# teensyShield1_4.net
KiCad netlist of a schematic drawn in EAGLE
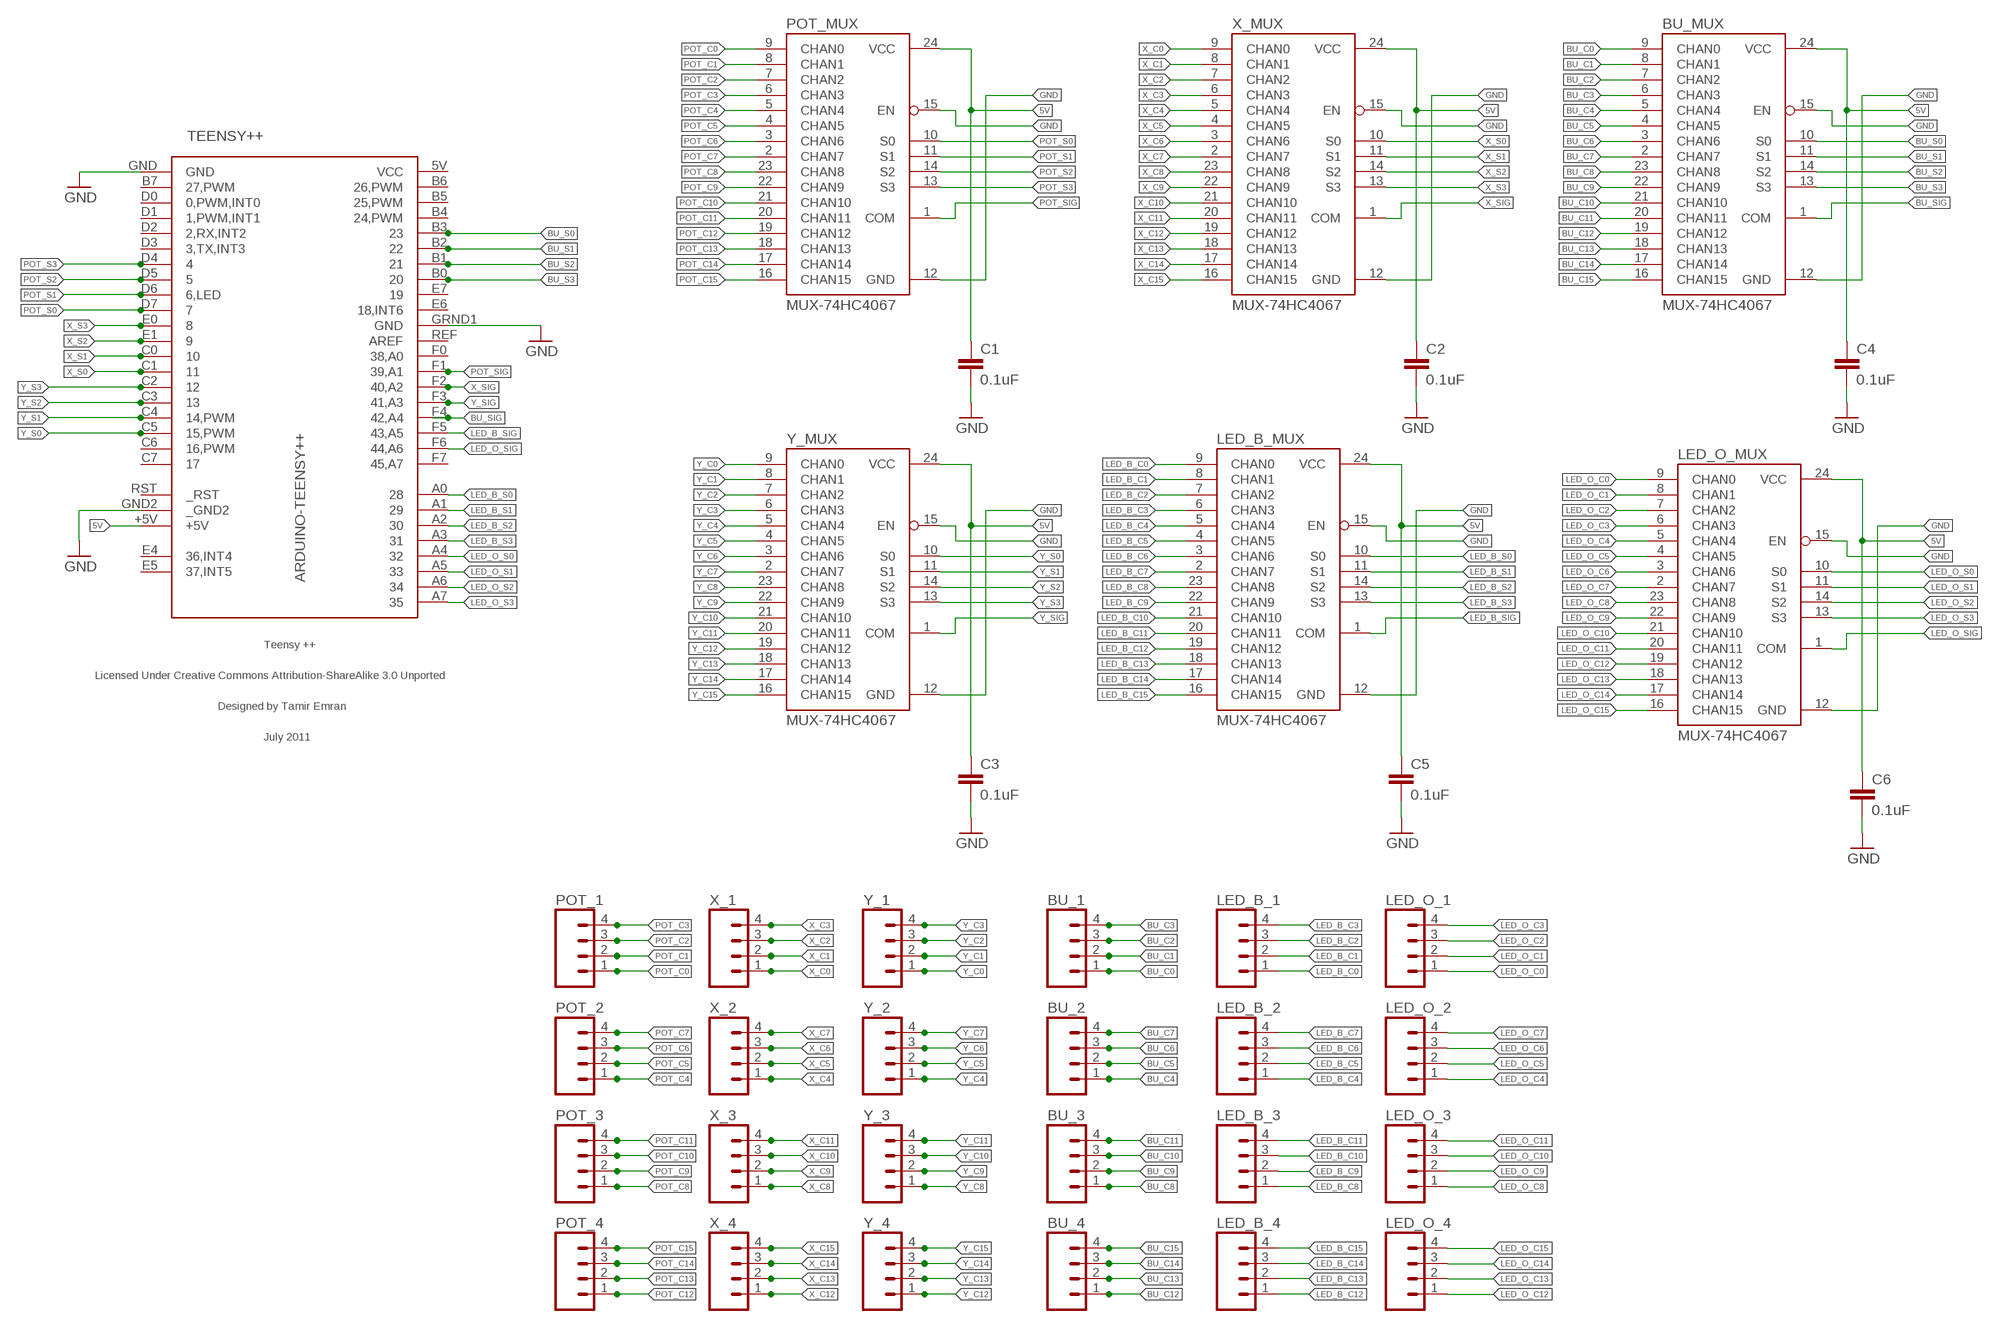
[diagram p0: schematic, sheet 1]

(export (version "E")
  (design (tool "Eeschema 10.0.6"))
  (components
    (comp (ref "BU_1")
      (value "M04NO_SILK_ALL_ROUND")
      (footprint "eagle-import:1X04_NO_SILK_ALL_ROUND")
      (libsource (lib "eagle-import") (part "M04NO_SILK_ALL_ROUND"))
    )
    (comp (ref "BU_2")
      (value "M04NO_SILK_ALL_ROUND")
      (footprint "eagle-import:1X04_NO_SILK_ALL_ROUND")
      (libsource (lib "eagle-import") (part "M04NO_SILK_ALL_ROUND"))
    )
    (comp (ref "BU_3")
      (value "M04NO_SILK_ALL_ROUND")
      (footprint "eagle-import:1X04_NO_SILK_ALL_ROUND")
      (libsource (lib "eagle-import") (part "M04NO_SILK_ALL_ROUND"))
    )
    (comp (ref "BU_4")
      (value "M04NO_SILK_ALL_ROUND")
      (footprint "eagle-import:1X04_NO_SILK_ALL_ROUND")
      (libsource (lib "eagle-import") (part "M04NO_SILK_ALL_ROUND"))
    )
    (comp (ref "BU_MUX")
      (value "MUX-74HC4067")
      (footprint "eagle-import:SSOP24")
      (libsource (lib "eagle-import") (part "MUX-74HC4067SMD"))
    )
    (comp (ref "C1")
      (value "0.1uF")
      (footprint "eagle-import:0603")
      (libsource (lib "eagle-import") (part "CAP0603"))
    )
    (comp (ref "C2")
      (value "0.1uF")
      (footprint "eagle-import:0603")
      (libsource (lib "eagle-import") (part "CAP0603"))
    )
    (comp (ref "C3")
      (value "0.1uF")
      (footprint "eagle-import:0603")
      (libsource (lib "eagle-import") (part "CAP0603"))
    )
    (comp (ref "C4")
      (value "0.1uF")
      (footprint "eagle-import:0603")
      (libsource (lib "eagle-import") (part "CAP0603"))
    )
    (comp (ref "C5")
      (value "0.1uF")
      (footprint "eagle-import:0603")
      (libsource (lib "eagle-import") (part "CAP0603"))
    )
    (comp (ref "C6")
      (value "0.1uF")
      (footprint "eagle-import:0603")
      (libsource (lib "eagle-import") (part "CAP0603"))
    )
    (comp (ref "LED_B_1")
      (value "M04NO_SILK_ALL_ROUND")
      (footprint "eagle-import:1X04_NO_SILK_ALL_ROUND")
      (libsource (lib "eagle-import") (part "M04NO_SILK_ALL_ROUND"))
    )
    (comp (ref "LED_B_2")
      (value "M04NO_SILK_ALL_ROUND")
      (footprint "eagle-import:1X04_NO_SILK_ALL_ROUND")
      (libsource (lib "eagle-import") (part "M04NO_SILK_ALL_ROUND"))
    )
    (comp (ref "LED_B_3")
      (value "M04NO_SILK_ALL_ROUND")
      (footprint "eagle-import:1X04_NO_SILK_ALL_ROUND")
      (libsource (lib "eagle-import") (part "M04NO_SILK_ALL_ROUND"))
    )
    (comp (ref "LED_B_4")
      (value "M04NO_SILK_ALL_ROUND")
      (footprint "eagle-import:1X04_NO_SILK_ALL_ROUND")
      (libsource (lib "eagle-import") (part "M04NO_SILK_ALL_ROUND"))
    )
    (comp (ref "LED_B_MUX")
      (value "MUX-74HC4067")
      (footprint "eagle-import:SSOP24")
      (libsource (lib "eagle-import") (part "MUX-74HC4067SMD"))
    )
    (comp (ref "LED_O_1")
      (value "M04NO_SILK_ALL_ROUND")
      (footprint "eagle-import:1X04_NO_SILK_ALL_ROUND")
      (libsource (lib "eagle-import") (part "M04NO_SILK_ALL_ROUND"))
    )
    (comp (ref "LED_O_2")
      (value "M04NO_SILK_ALL_ROUND")
      (footprint "eagle-import:1X04_NO_SILK_ALL_ROUND")
      (libsource (lib "eagle-import") (part "M04NO_SILK_ALL_ROUND"))
    )
    (comp (ref "LED_O_3")
      (value "M04NO_SILK_ALL_ROUND")
      (footprint "eagle-import:1X04_NO_SILK_ALL_ROUND")
      (libsource (lib "eagle-import") (part "M04NO_SILK_ALL_ROUND"))
    )
    (comp (ref "LED_O_4")
      (value "M04NO_SILK_ALL_ROUND")
      (footprint "eagle-import:1X04_NO_SILK_ALL_ROUND")
      (libsource (lib "eagle-import") (part "M04NO_SILK_ALL_ROUND"))
    )
    (comp (ref "LED_O_MUX")
      (value "MUX-74HC4067")
      (footprint "eagle-import:SSOP24")
      (libsource (lib "eagle-import") (part "MUX-74HC4067SMD"))
    )
    (comp (ref "POT_1")
      (value "M04NO_SILK_ALL_ROUND")
      (footprint "eagle-import:1X04_NO_SILK_ALL_ROUND")
      (libsource (lib "eagle-import") (part "M04NO_SILK_ALL_ROUND"))
    )
    (comp (ref "POT_2")
      (value "M04NO_SILK_ALL_ROUND")
      (footprint "eagle-import:1X04_NO_SILK_ALL_ROUND")
      (libsource (lib "eagle-import") (part "M04NO_SILK_ALL_ROUND"))
    )
    (comp (ref "POT_3")
      (value "M04NO_SILK_ALL_ROUND")
      (footprint "eagle-import:1X04_NO_SILK_ALL_ROUND")
      (libsource (lib "eagle-import") (part "M04NO_SILK_ALL_ROUND"))
    )
    (comp (ref "POT_4")
      (value "M04NO_SILK_ALL_ROUND")
      (footprint "eagle-import:1X04_NO_SILK_ALL_ROUND")
      (libsource (lib "eagle-import") (part "M04NO_SILK_ALL_ROUND"))
    )
    (comp (ref "POT_MUX")
      (value "MUX-74HC4067")
      (footprint "eagle-import:SSOP24")
      (libsource (lib "eagle-import") (part "MUX-74HC4067SMD"))
    )
    (comp (ref "TEENSY++")
      (value "ARDUINO-TEENSY++")
      (footprint "eagle-import:TEENSY++")
      (libsource (lib "eagle-import") (part "ARDUINO-TEENSY++"))
    )
    (comp (ref "X_1")
      (value "M04NO_SILK_ALL_ROUND")
      (footprint "eagle-import:1X04_NO_SILK_ALL_ROUND")
      (libsource (lib "eagle-import") (part "M04NO_SILK_ALL_ROUND"))
    )
    (comp (ref "X_2")
      (value "M04NO_SILK_ALL_ROUND")
      (footprint "eagle-import:1X04_NO_SILK_ALL_ROUND")
      (libsource (lib "eagle-import") (part "M04NO_SILK_ALL_ROUND"))
    )
    (comp (ref "X_3")
      (value "M04NO_SILK_ALL_ROUND")
      (footprint "eagle-import:1X04_NO_SILK_ALL_ROUND")
      (libsource (lib "eagle-import") (part "M04NO_SILK_ALL_ROUND"))
    )
    (comp (ref "X_4")
      (value "M04NO_SILK_ALL_ROUND")
      (footprint "eagle-import:1X04_NO_SILK_ALL_ROUND")
      (libsource (lib "eagle-import") (part "M04NO_SILK_ALL_ROUND"))
    )
    (comp (ref "X_MUX")
      (value "MUX-74HC4067")
      (footprint "eagle-import:SSOP24")
      (libsource (lib "eagle-import") (part "MUX-74HC4067SMD"))
    )
    (comp (ref "Y_1")
      (value "M04NO_SILK_ALL_ROUND")
      (footprint "eagle-import:1X04_NO_SILK_ALL_ROUND")
      (libsource (lib "eagle-import") (part "M04NO_SILK_ALL_ROUND"))
    )
    (comp (ref "Y_2")
      (value "M04NO_SILK_ALL_ROUND")
      (footprint "eagle-import:1X04_NO_SILK_ALL_ROUND")
      (libsource (lib "eagle-import") (part "M04NO_SILK_ALL_ROUND"))
    )
    (comp (ref "Y_3")
      (value "M04NO_SILK_ALL_ROUND")
      (footprint "eagle-import:1X04_NO_SILK_ALL_ROUND")
      (libsource (lib "eagle-import") (part "M04NO_SILK_ALL_ROUND"))
    )
    (comp (ref "Y_4")
      (value "M04NO_SILK_ALL_ROUND")
      (footprint "eagle-import:1X04_NO_SILK_ALL_ROUND")
      (libsource (lib "eagle-import") (part "M04NO_SILK_ALL_ROUND"))
    )
    (comp (ref "Y_MUX")
      (value "MUX-74HC4067")
      (footprint "eagle-import:SSOP24")
      (libsource (lib "eagle-import") (part "MUX-74HC4067SMD"))
    )
  )
  (nets
    (net (code "1") (name "/VCC") (class "Default")
      (node (ref "TEENSY++") (pin "5V") (pinfunction "VCC_5V") (pintype "power_in"))
    )
    (net (code "2") (name "5V") (class "Default")
      (node (ref "BU_MUX") (pin "24") (pinfunction "VCC_24") (pintype "bidirectional"))
      (node (ref "C1") (pin "1") (pinfunction "1_1") (pintype "passive"))
      (node (ref "C2") (pin "1") (pinfunction "1_1") (pintype "passive"))
      (node (ref "C3") (pin "1") (pinfunction "1_1") (pintype "passive"))
      (node (ref "C4") (pin "1") (pinfunction "1_1") (pintype "passive"))
      (node (ref "C5") (pin "1") (pinfunction "1_1") (pintype "passive"))
      (node (ref "C6") (pin "1") (pinfunction "1_1") (pintype "passive"))
      (node (ref "LED_B_MUX") (pin "24") (pinfunction "VCC_24") (pintype "bidirectional"))
      (node (ref "LED_O_MUX") (pin "24") (pinfunction "VCC_24") (pintype "bidirectional"))
      (node (ref "POT_MUX") (pin "24") (pinfunction "VCC_24") (pintype "bidirectional"))
      (node (ref "X_MUX") (pin "24") (pinfunction "VCC_24") (pintype "bidirectional"))
      (node (ref "Y_MUX") (pin "24") (pinfunction "VCC_24") (pintype "bidirectional"))
    )
    (net (code "3") (name "BU_C0") (class "Default")
      (node (ref "BU_1") (pin "1") (pinfunction "1_1") (pintype "passive"))
      (node (ref "BU_MUX") (pin "9") (pinfunction "CHAN0_9") (pintype "bidirectional"))
    )
    (net (code "4") (name "BU_C1") (class "Default")
      (node (ref "BU_1") (pin "2") (pinfunction "2_2") (pintype "passive"))
      (node (ref "BU_MUX") (pin "8") (pinfunction "CHAN1_8") (pintype "bidirectional"))
    )
    (net (code "5") (name "BU_C2") (class "Default")
      (node (ref "BU_1") (pin "3") (pinfunction "3_3") (pintype "passive"))
      (node (ref "BU_MUX") (pin "7") (pinfunction "CHAN2_7") (pintype "bidirectional"))
    )
    (net (code "6") (name "BU_C3") (class "Default")
      (node (ref "BU_1") (pin "4") (pinfunction "4_4") (pintype "passive"))
      (node (ref "BU_MUX") (pin "6") (pinfunction "CHAN3_6") (pintype "bidirectional"))
    )
    (net (code "7") (name "BU_C4") (class "Default")
      (node (ref "BU_2") (pin "1") (pinfunction "1_1") (pintype "passive"))
      (node (ref "BU_MUX") (pin "5") (pinfunction "CHAN4_5") (pintype "bidirectional"))
    )
    (net (code "8") (name "BU_C5") (class "Default")
      (node (ref "BU_2") (pin "2") (pinfunction "2_2") (pintype "passive"))
      (node (ref "BU_MUX") (pin "4") (pinfunction "CHAN5_4") (pintype "bidirectional"))
    )
    (net (code "9") (name "BU_C6") (class "Default")
      (node (ref "BU_2") (pin "3") (pinfunction "3_3") (pintype "passive"))
      (node (ref "BU_MUX") (pin "3") (pinfunction "CHAN6_3") (pintype "bidirectional"))
    )
    (net (code "10") (name "BU_C7") (class "Default")
      (node (ref "BU_2") (pin "4") (pinfunction "4_4") (pintype "passive"))
      (node (ref "BU_MUX") (pin "2") (pinfunction "CHAN7_2") (pintype "bidirectional"))
    )
    (net (code "11") (name "BU_C8") (class "Default")
      (node (ref "BU_3") (pin "1") (pinfunction "1_1") (pintype "passive"))
      (node (ref "BU_MUX") (pin "23") (pinfunction "CHAN8_23") (pintype "bidirectional"))
    )
    (net (code "12") (name "BU_C9") (class "Default")
      (node (ref "BU_3") (pin "2") (pinfunction "2_2") (pintype "passive"))
      (node (ref "BU_MUX") (pin "22") (pinfunction "CHAN9_22") (pintype "bidirectional"))
    )
    (net (code "13") (name "BU_C10") (class "Default")
      (node (ref "BU_3") (pin "3") (pinfunction "3_3") (pintype "passive"))
      (node (ref "BU_MUX") (pin "21") (pinfunction "CHAN10_21") (pintype "bidirectional"))
    )
    (net (code "14") (name "BU_C11") (class "Default")
      (node (ref "BU_3") (pin "4") (pinfunction "4_4") (pintype "passive"))
      (node (ref "BU_MUX") (pin "20") (pinfunction "CHAN11_20") (pintype "bidirectional"))
    )
    (net (code "15") (name "BU_C12") (class "Default")
      (node (ref "BU_4") (pin "1") (pinfunction "1_1") (pintype "passive"))
      (node (ref "BU_MUX") (pin "19") (pinfunction "CHAN12_19") (pintype "bidirectional"))
    )
    (net (code "16") (name "BU_C13") (class "Default")
      (node (ref "BU_4") (pin "2") (pinfunction "2_2") (pintype "passive"))
      (node (ref "BU_MUX") (pin "18") (pinfunction "CHAN13_18") (pintype "bidirectional"))
    )
    (net (code "17") (name "BU_C14") (class "Default")
      (node (ref "BU_4") (pin "3") (pinfunction "3_3") (pintype "passive"))
      (node (ref "BU_MUX") (pin "17") (pinfunction "CHAN14_17") (pintype "bidirectional"))
    )
    (net (code "18") (name "BU_C15") (class "Default")
      (node (ref "BU_4") (pin "4") (pinfunction "4_4") (pintype "passive"))
      (node (ref "BU_MUX") (pin "16") (pinfunction "CHAN15_16") (pintype "bidirectional"))
    )
    (net (code "19") (name "BU_S0") (class "Default")
      (node (ref "BU_MUX") (pin "10") (pinfunction "S0_10") (pintype "input"))
      (node (ref "TEENSY++") (pin "B3") (pinfunction "23_B3") (pintype "bidirectional"))
    )
    (net (code "20") (name "BU_S1") (class "Default")
      (node (ref "BU_MUX") (pin "11") (pinfunction "S1_11") (pintype "input"))
      (node (ref "TEENSY++") (pin "B2") (pinfunction "22_B2") (pintype "bidirectional"))
    )
    (net (code "21") (name "BU_S2") (class "Default")
      (node (ref "BU_MUX") (pin "14") (pinfunction "S2_14") (pintype "input"))
      (node (ref "TEENSY++") (pin "B1") (pinfunction "21_B1") (pintype "bidirectional"))
    )
    (net (code "22") (name "BU_S3") (class "Default")
      (node (ref "BU_MUX") (pin "13") (pinfunction "S3_13") (pintype "input"))
      (node (ref "TEENSY++") (pin "B0") (pinfunction "20_B0") (pintype "bidirectional"))
    )
    (net (code "23") (name "BU_SIG") (class "Default")
      (node (ref "BU_MUX") (pin "1") (pinfunction "COM_1") (pintype "bidirectional"))
      (node (ref "TEENSY++") (pin "F4") (pinfunction "42,A4_F4") (pintype "bidirectional"))
    )
    (net (code "24") (name "GND") (class "Default")
      (node (ref "BU_MUX") (pin "12") (pinfunction "GND_12") (pintype "bidirectional"))
      (node (ref "BU_MUX") (pin "15") (pinfunction "EN_15") (pintype "input"))
      (node (ref "C1") (pin "2") (pinfunction "2_2") (pintype "passive"))
      (node (ref "C2") (pin "2") (pinfunction "2_2") (pintype "passive"))
      (node (ref "C3") (pin "2") (pinfunction "2_2") (pintype "passive"))
      (node (ref "C4") (pin "2") (pinfunction "2_2") (pintype "passive"))
      (node (ref "C5") (pin "2") (pinfunction "2_2") (pintype "passive"))
      (node (ref "C6") (pin "2") (pinfunction "2_2") (pintype "passive"))
      (node (ref "LED_B_MUX") (pin "12") (pinfunction "GND_12") (pintype "bidirectional"))
      (node (ref "LED_B_MUX") (pin "15") (pinfunction "EN_15") (pintype "input"))
      (node (ref "LED_O_MUX") (pin "12") (pinfunction "GND_12") (pintype "bidirectional"))
      (node (ref "LED_O_MUX") (pin "15") (pinfunction "EN_15") (pintype "input"))
      (node (ref "POT_MUX") (pin "12") (pinfunction "GND_12") (pintype "bidirectional"))
      (node (ref "POT_MUX") (pin "15") (pinfunction "EN_15") (pintype "input"))
      (node (ref "TEENSY++") (pin "GND") (pinfunction "GND_GND") (pintype "power_in"))
      (node (ref "TEENSY++") (pin "GND2") (pinfunction "_GND2_GND2") (pintype "power_in"))
      (node (ref "TEENSY++") (pin "GRND1") (pinfunction "GND_GRND1") (pintype "power_in"))
      (node (ref "X_MUX") (pin "12") (pinfunction "GND_12") (pintype "bidirectional"))
      (node (ref "X_MUX") (pin "15") (pinfunction "EN_15") (pintype "input"))
      (node (ref "Y_MUX") (pin "12") (pinfunction "GND_12") (pintype "bidirectional"))
      (node (ref "Y_MUX") (pin "15") (pinfunction "EN_15") (pintype "input"))
    )
    (net (code "25") (name "LED_B_C0") (class "Default")
      (node (ref "LED_B_1") (pin "1") (pinfunction "1_1") (pintype "passive"))
      (node (ref "LED_B_MUX") (pin "9") (pinfunction "CHAN0_9") (pintype "bidirectional"))
    )
    (net (code "26") (name "LED_B_C1") (class "Default")
      (node (ref "LED_B_1") (pin "2") (pinfunction "2_2") (pintype "passive"))
      (node (ref "LED_B_MUX") (pin "8") (pinfunction "CHAN1_8") (pintype "bidirectional"))
    )
    (net (code "27") (name "LED_B_C2") (class "Default")
      (node (ref "LED_B_1") (pin "3") (pinfunction "3_3") (pintype "passive"))
      (node (ref "LED_B_MUX") (pin "7") (pinfunction "CHAN2_7") (pintype "bidirectional"))
    )
    (net (code "28") (name "LED_B_C3") (class "Default")
      (node (ref "LED_B_1") (pin "4") (pinfunction "4_4") (pintype "passive"))
      (node (ref "LED_B_MUX") (pin "6") (pinfunction "CHAN3_6") (pintype "bidirectional"))
    )
    (net (code "29") (name "LED_B_C4") (class "Default")
      (node (ref "LED_B_2") (pin "1") (pinfunction "1_1") (pintype "passive"))
      (node (ref "LED_B_MUX") (pin "5") (pinfunction "CHAN4_5") (pintype "bidirectional"))
    )
    (net (code "30") (name "LED_B_C5") (class "Default")
      (node (ref "LED_B_2") (pin "2") (pinfunction "2_2") (pintype "passive"))
      (node (ref "LED_B_MUX") (pin "4") (pinfunction "CHAN5_4") (pintype "bidirectional"))
    )
    (net (code "31") (name "LED_B_C6") (class "Default")
      (node (ref "LED_B_2") (pin "3") (pinfunction "3_3") (pintype "passive"))
      (node (ref "LED_B_MUX") (pin "3") (pinfunction "CHAN6_3") (pintype "bidirectional"))
    )
    (net (code "32") (name "LED_B_C7") (class "Default")
      (node (ref "LED_B_2") (pin "4") (pinfunction "4_4") (pintype "passive"))
      (node (ref "LED_B_MUX") (pin "2") (pinfunction "CHAN7_2") (pintype "bidirectional"))
    )
    (net (code "33") (name "LED_B_C8") (class "Default")
      (node (ref "LED_B_3") (pin "1") (pinfunction "1_1") (pintype "passive"))
      (node (ref "LED_B_MUX") (pin "23") (pinfunction "CHAN8_23") (pintype "bidirectional"))
    )
    (net (code "34") (name "LED_B_C9") (class "Default")
      (node (ref "LED_B_3") (pin "2") (pinfunction "2_2") (pintype "passive"))
      (node (ref "LED_B_MUX") (pin "22") (pinfunction "CHAN9_22") (pintype "bidirectional"))
    )
    (net (code "35") (name "LED_B_C10") (class "Default")
      (node (ref "LED_B_3") (pin "3") (pinfunction "3_3") (pintype "passive"))
      (node (ref "LED_B_MUX") (pin "21") (pinfunction "CHAN10_21") (pintype "bidirectional"))
    )
    (net (code "36") (name "LED_B_C11") (class "Default")
      (node (ref "LED_B_3") (pin "4") (pinfunction "4_4") (pintype "passive"))
      (node (ref "LED_B_MUX") (pin "20") (pinfunction "CHAN11_20") (pintype "bidirectional"))
    )
    (net (code "37") (name "LED_B_C12") (class "Default")
      (node (ref "LED_B_4") (pin "1") (pinfunction "1_1") (pintype "passive"))
      (node (ref "LED_B_MUX") (pin "19") (pinfunction "CHAN12_19") (pintype "bidirectional"))
    )
    (net (code "38") (name "LED_B_C13") (class "Default")
      (node (ref "LED_B_4") (pin "2") (pinfunction "2_2") (pintype "passive"))
      (node (ref "LED_B_MUX") (pin "18") (pinfunction "CHAN13_18") (pintype "bidirectional"))
    )
    (net (code "39") (name "LED_B_C14") (class "Default")
      (node (ref "LED_B_4") (pin "3") (pinfunction "3_3") (pintype "passive"))
      (node (ref "LED_B_MUX") (pin "17") (pinfunction "CHAN14_17") (pintype "bidirectional"))
    )
    (net (code "40") (name "LED_B_C15") (class "Default")
      (node (ref "LED_B_4") (pin "4") (pinfunction "4_4") (pintype "passive"))
      (node (ref "LED_B_MUX") (pin "16") (pinfunction "CHAN15_16") (pintype "bidirectional"))
    )
    (net (code "41") (name "LED_B_S0") (class "Default")
      (node (ref "LED_B_MUX") (pin "10") (pinfunction "S0_10") (pintype "input"))
      (node (ref "TEENSY++") (pin "A0") (pinfunction "28_A0") (pintype "bidirectional"))
    )
    (net (code "42") (name "LED_B_S1") (class "Default")
      (node (ref "LED_B_MUX") (pin "11") (pinfunction "S1_11") (pintype "input"))
      (node (ref "TEENSY++") (pin "A1") (pinfunction "29_A1") (pintype "bidirectional"))
    )
    (net (code "43") (name "LED_B_S2") (class "Default")
      (node (ref "LED_B_MUX") (pin "14") (pinfunction "S2_14") (pintype "input"))
      (node (ref "TEENSY++") (pin "A2") (pinfunction "30_A2") (pintype "bidirectional"))
    )
    (net (code "44") (name "LED_B_S3") (class "Default")
      (node (ref "LED_B_MUX") (pin "13") (pinfunction "S3_13") (pintype "input"))
      (node (ref "TEENSY++") (pin "A3") (pinfunction "31_A3") (pintype "bidirectional"))
    )
    (net (code "45") (name "LED_B_SIG") (class "Default")
      (node (ref "LED_B_MUX") (pin "1") (pinfunction "COM_1") (pintype "bidirectional"))
    )
    (net (code "46") (name "LED_O_C0") (class "Default")
      (node (ref "LED_O_1") (pin "1") (pinfunction "1_1") (pintype "passive"))
      (node (ref "LED_O_MUX") (pin "9") (pinfunction "CHAN0_9") (pintype "bidirectional"))
    )
    (net (code "47") (name "LED_O_C1") (class "Default")
      (node (ref "LED_O_1") (pin "2") (pinfunction "2_2") (pintype "passive"))
      (node (ref "LED_O_MUX") (pin "8") (pinfunction "CHAN1_8") (pintype "bidirectional"))
    )
    (net (code "48") (name "LED_O_C2") (class "Default")
      (node (ref "LED_O_1") (pin "3") (pinfunction "3_3") (pintype "passive"))
      (node (ref "LED_O_MUX") (pin "7") (pinfunction "CHAN2_7") (pintype "bidirectional"))
    )
    (net (code "49") (name "LED_O_C3") (class "Default")
      (node (ref "LED_O_1") (pin "4") (pinfunction "4_4") (pintype "passive"))
      (node (ref "LED_O_MUX") (pin "6") (pinfunction "CHAN3_6") (pintype "bidirectional"))
    )
    (net (code "50") (name "LED_O_C4") (class "Default")
      (node (ref "LED_O_2") (pin "1") (pinfunction "1_1") (pintype "passive"))
      (node (ref "LED_O_MUX") (pin "5") (pinfunction "CHAN4_5") (pintype "bidirectional"))
    )
    (net (code "51") (name "LED_O_C5") (class "Default")
      (node (ref "LED_O_2") (pin "2") (pinfunction "2_2") (pintype "passive"))
      (node (ref "LED_O_MUX") (pin "4") (pinfunction "CHAN5_4") (pintype "bidirectional"))
    )
    (net (code "52") (name "LED_O_C6") (class "Default")
      (node (ref "LED_O_2") (pin "3") (pinfunction "3_3") (pintype "passive"))
      (node (ref "LED_O_MUX") (pin "3") (pinfunction "CHAN6_3") (pintype "bidirectional"))
    )
    (net (code "53") (name "LED_O_C7") (class "Default")
      (node (ref "LED_O_2") (pin "4") (pinfunction "4_4") (pintype "passive"))
      (node (ref "LED_O_MUX") (pin "2") (pinfunction "CHAN7_2") (pintype "bidirectional"))
    )
    (net (code "54") (name "LED_O_C8") (class "Default")
      (node (ref "LED_O_3") (pin "1") (pinfunction "1_1") (pintype "passive"))
      (node (ref "LED_O_MUX") (pin "23") (pinfunction "CHAN8_23") (pintype "bidirectional"))
    )
    (net (code "55") (name "LED_O_C9") (class "Default")
      (node (ref "LED_O_3") (pin "2") (pinfunction "2_2") (pintype "passive"))
      (node (ref "LED_O_MUX") (pin "22") (pinfunction "CHAN9_22") (pintype "bidirectional"))
    )
    (net (code "56") (name "LED_O_C10") (class "Default")
      (node (ref "LED_O_3") (pin "3") (pinfunction "3_3") (pintype "passive"))
      (node (ref "LED_O_MUX") (pin "21") (pinfunction "CHAN10_21") (pintype "bidirectional"))
    )
    (net (code "57") (name "LED_O_C11") (class "Default")
      (node (ref "LED_O_3") (pin "4") (pinfunction "4_4") (pintype "passive"))
      (node (ref "LED_O_MUX") (pin "20") (pinfunction "CHAN11_20") (pintype "bidirectional"))
    )
    (net (code "58") (name "LED_O_C12") (class "Default")
      (node (ref "LED_O_4") (pin "1") (pinfunction "1_1") (pintype "passive"))
      (node (ref "LED_O_MUX") (pin "19") (pinfunction "CHAN12_19") (pintype "bidirectional"))
    )
    (net (code "59") (name "LED_O_C13") (class "Default")
      (node (ref "LED_O_4") (pin "2") (pinfunction "2_2") (pintype "passive"))
      (node (ref "LED_O_MUX") (pin "18") (pinfunction "CHAN13_18") (pintype "bidirectional"))
    )
    (net (code "60") (name "LED_O_C14") (class "Default")
      (node (ref "LED_O_4") (pin "3") (pinfunction "3_3") (pintype "passive"))
      (node (ref "LED_O_MUX") (pin "17") (pinfunction "CHAN14_17") (pintype "bidirectional"))
    )
    (net (code "61") (name "LED_O_C15") (class "Default")
      (node (ref "LED_O_4") (pin "4") (pinfunction "4_4") (pintype "passive"))
      (node (ref "LED_O_MUX") (pin "16") (pinfunction "CHAN15_16") (pintype "bidirectional"))
    )
    (net (code "62") (name "LED_O_S0") (class "Default")
      (node (ref "LED_O_MUX") (pin "10") (pinfunction "S0_10") (pintype "input"))
      (node (ref "TEENSY++") (pin "A4") (pinfunction "32_A4") (pintype "bidirectional"))
    )
    (net (code "63") (name "LED_O_S1") (class "Default")
      (node (ref "LED_O_MUX") (pin "11") (pinfunction "S1_11") (pintype "input"))
      (node (ref "TEENSY++") (pin "A5") (pinfunction "33_A5") (pintype "bidirectional"))
    )
    (net (code "64") (name "LED_O_S2") (class "Default")
      (node (ref "LED_O_MUX") (pin "14") (pinfunction "S2_14") (pintype "input"))
      (node (ref "TEENSY++") (pin "A6") (pinfunction "34_A6") (pintype "bidirectional"))
    )
    (net (code "65") (name "LED_O_S3") (class "Default")
      (node (ref "LED_O_MUX") (pin "13") (pinfunction "S3_13") (pintype "input"))
      (node (ref "TEENSY++") (pin "A7") (pinfunction "35_A7") (pintype "bidirectional"))
    )
    (net (code "66") (name "LED_O_SIG") (class "Default")
      (node (ref "LED_O_MUX") (pin "1") (pinfunction "COM_1") (pintype "bidirectional"))
    )
    (net (code "67") (name "POT_C0") (class "Default")
      (node (ref "POT_1") (pin "1") (pinfunction "1_1") (pintype "passive"))
      (node (ref "POT_MUX") (pin "9") (pinfunction "CHAN0_9") (pintype "bidirectional"))
    )
    (net (code "68") (name "POT_C1") (class "Default")
      (node (ref "POT_1") (pin "2") (pinfunction "2_2") (pintype "passive"))
      (node (ref "POT_MUX") (pin "8") (pinfunction "CHAN1_8") (pintype "bidirectional"))
    )
    (net (code "69") (name "POT_C2") (class "Default")
      (node (ref "POT_1") (pin "3") (pinfunction "3_3") (pintype "passive"))
      (node (ref "POT_MUX") (pin "7") (pinfunction "CHAN2_7") (pintype "bidirectional"))
    )
    (net (code "70") (name "POT_C3") (class "Default")
      (node (ref "POT_1") (pin "4") (pinfunction "4_4") (pintype "passive"))
      (node (ref "POT_MUX") (pin "6") (pinfunction "CHAN3_6") (pintype "bidirectional"))
    )
    (net (code "71") (name "POT_C4") (class "Default")
      (node (ref "POT_2") (pin "1") (pinfunction "1_1") (pintype "passive"))
      (node (ref "POT_MUX") (pin "5") (pinfunction "CHAN4_5") (pintype "bidirectional"))
    )
    (net (code "72") (name "POT_C5") (class "Default")
      (node (ref "POT_2") (pin "2") (pinfunction "2_2") (pintype "passive"))
      (node (ref "POT_MUX") (pin "4") (pinfunction "CHAN5_4") (pintype "bidirectional"))
    )
    (net (code "73") (name "POT_C6") (class "Default")
      (node (ref "POT_2") (pin "3") (pinfunction "3_3") (pintype "passive"))
      (node (ref "POT_MUX") (pin "3") (pinfunction "CHAN6_3") (pintype "bidirectional"))
    )
    (net (code "74") (name "POT_C7") (class "Default")
      (node (ref "POT_2") (pin "4") (pinfunction "4_4") (pintype "passive"))
      (node (ref "POT_MUX") (pin "2") (pinfunction "CHAN7_2") (pintype "bidirectional"))
    )
    (net (code "75") (name "POT_C8") (class "Default")
      (node (ref "POT_3") (pin "1") (pinfunction "1_1") (pintype "passive"))
      (node (ref "POT_MUX") (pin "23") (pinfunction "CHAN8_23") (pintype "bidirectional"))
    )
    (net (code "76") (name "POT_C9") (class "Default")
      (node (ref "POT_3") (pin "2") (pinfunction "2_2") (pintype "passive"))
      (node (ref "POT_MUX") (pin "22") (pinfunction "CHAN9_22") (pintype "bidirectional"))
    )
    (net (code "77") (name "POT_C10") (class "Default")
      (node (ref "POT_3") (pin "3") (pinfunction "3_3") (pintype "passive"))
      (node (ref "POT_MUX") (pin "21") (pinfunction "CHAN10_21") (pintype "bidirectional"))
    )
    (net (code "78") (name "POT_C11") (class "Default")
      (node (ref "POT_3") (pin "4") (pinfunction "4_4") (pintype "passive"))
      (node (ref "POT_MUX") (pin "20") (pinfunction "CHAN11_20") (pintype "bidirectional"))
    )
    (net (code "79") (name "POT_C12") (class "Default")
      (node (ref "POT_4") (pin "1") (pinfunction "1_1") (pintype "passive"))
      (node (ref "POT_MUX") (pin "19") (pinfunction "CHAN12_19") (pintype "bidirectional"))
    )
    (net (code "80") (name "POT_C13") (class "Default")
      (node (ref "POT_4") (pin "2") (pinfunction "2_2") (pintype "passive"))
      (node (ref "POT_MUX") (pin "18") (pinfunction "CHAN13_18") (pintype "bidirectional"))
    )
    (net (code "81") (name "POT_C14") (class "Default")
      (node (ref "POT_4") (pin "3") (pinfunction "3_3") (pintype "passive"))
      (node (ref "POT_MUX") (pin "17") (pinfunction "CHAN14_17") (pintype "bidirectional"))
    )
    (net (code "82") (name "POT_C15") (class "Default")
      (node (ref "POT_4") (pin "4") (pinfunction "4_4") (pintype "passive"))
      (node (ref "POT_MUX") (pin "16") (pinfunction "CHAN15_16") (pintype "bidirectional"))
    )
    (net (code "83") (name "POT_S0") (class "Default")
      (node (ref "POT_MUX") (pin "10") (pinfunction "S0_10") (pintype "input"))
      (node (ref "TEENSY++") (pin "D7") (pinfunction "7_D7") (pintype "bidirectional"))
    )
    (net (code "84") (name "POT_S1") (class "Default")
      (node (ref "POT_MUX") (pin "11") (pinfunction "S1_11") (pintype "input"))
      (node (ref "TEENSY++") (pin "D6") (pinfunction "6,LED_D6") (pintype "bidirectional"))
    )
    (net (code "85") (name "POT_S2") (class "Default")
      (node (ref "POT_MUX") (pin "14") (pinfunction "S2_14") (pintype "input"))
      (node (ref "TEENSY++") (pin "D5") (pinfunction "5_D5") (pintype "bidirectional"))
    )
    (net (code "86") (name "POT_S3") (class "Default")
      (node (ref "POT_MUX") (pin "13") (pinfunction "S3_13") (pintype "input"))
      (node (ref "TEENSY++") (pin "D4") (pinfunction "4_D4") (pintype "bidirectional"))
    )
    (net (code "87") (name "POT_SIG") (class "Default")
      (node (ref "POT_MUX") (pin "1") (pinfunction "COM_1") (pintype "bidirectional"))
    )
    (net (code "88") (name "X_C0") (class "Default")
      (node (ref "X_1") (pin "1") (pinfunction "1_1") (pintype "passive"))
      (node (ref "X_MUX") (pin "9") (pinfunction "CHAN0_9") (pintype "bidirectional"))
    )
    (net (code "89") (name "X_C1") (class "Default")
      (node (ref "X_1") (pin "2") (pinfunction "2_2") (pintype "passive"))
      (node (ref "X_MUX") (pin "8") (pinfunction "CHAN1_8") (pintype "bidirectional"))
    )
    (net (code "90") (name "X_C2") (class "Default")
      (node (ref "X_1") (pin "3") (pinfunction "3_3") (pintype "passive"))
      (node (ref "X_MUX") (pin "7") (pinfunction "CHAN2_7") (pintype "bidirectional"))
    )
    (net (code "91") (name "X_C3") (class "Default")
      (node (ref "X_1") (pin "4") (pinfunction "4_4") (pintype "passive"))
      (node (ref "X_MUX") (pin "6") (pinfunction "CHAN3_6") (pintype "bidirectional"))
    )
    (net (code "92") (name "X_C4") (class "Default")
      (node (ref "X_2") (pin "1") (pinfunction "1_1") (pintype "passive"))
      (node (ref "X_MUX") (pin "5") (pinfunction "CHAN4_5") (pintype "bidirectional"))
    )
    (net (code "93") (name "X_C5") (class "Default")
      (node (ref "X_2") (pin "2") (pinfunction "2_2") (pintype "passive"))
      (node (ref "X_MUX") (pin "4") (pinfunction "CHAN5_4") (pintype "bidirectional"))
    )
    (net (code "94") (name "X_C6") (class "Default")
      (node (ref "X_2") (pin "3") (pinfunction "3_3") (pintype "passive"))
      (node (ref "X_MUX") (pin "3") (pinfunction "CHAN6_3") (pintype "bidirectional"))
    )
    (net (code "95") (name "X_C7") (class "Default")
      (node (ref "X_2") (pin "4") (pinfunction "4_4") (pintype "passive"))
      (node (ref "X_MUX") (pin "2") (pinfunction "CHAN7_2") (pintype "bidirectional"))
    )
    (net (code "96") (name "X_C8") (class "Default")
      (node (ref "X_3") (pin "1") (pinfunction "1_1") (pintype "passive"))
      (node (ref "X_MUX") (pin "23") (pinfunction "CHAN8_23") (pintype "bidirectional"))
    )
    (net (code "97") (name "X_C9") (class "Default")
      (node (ref "X_3") (pin "2") (pinfunction "2_2") (pintype "passive"))
      (node (ref "X_MUX") (pin "22") (pinfunction "CHAN9_22") (pintype "bidirectional"))
    )
    (net (code "98") (name "X_C10") (class "Default")
      (node (ref "X_3") (pin "3") (pinfunction "3_3") (pintype "passive"))
      (node (ref "X_MUX") (pin "21") (pinfunction "CHAN10_21") (pintype "bidirectional"))
    )
    (net (code "99") (name "X_C11") (class "Default")
      (node (ref "X_3") (pin "4") (pinfunction "4_4") (pintype "passive"))
      (node (ref "X_MUX") (pin "20") (pinfunction "CHAN11_20") (pintype "bidirectional"))
    )
    (net (code "100") (name "X_C12") (class "Default")
      (node (ref "X_4") (pin "1") (pinfunction "1_1") (pintype "passive"))
      (node (ref "X_MUX") (pin "19") (pinfunction "CHAN12_19") (pintype "bidirectional"))
    )
    (net (code "101") (name "X_C13") (class "Default")
      (node (ref "X_4") (pin "2") (pinfunction "2_2") (pintype "passive"))
      (node (ref "X_MUX") (pin "18") (pinfunction "CHAN13_18") (pintype "bidirectional"))
    )
    (net (code "102") (name "X_C14") (class "Default")
      (node (ref "X_4") (pin "3") (pinfunction "3_3") (pintype "passive"))
      (node (ref "X_MUX") (pin "17") (pinfunction "CHAN14_17") (pintype "bidirectional"))
    )
    (net (code "103") (name "X_C15") (class "Default")
      (node (ref "X_4") (pin "4") (pinfunction "4_4") (pintype "passive"))
      (node (ref "X_MUX") (pin "16") (pinfunction "CHAN15_16") (pintype "bidirectional"))
    )
    (net (code "104") (name "X_S0") (class "Default")
      (node (ref "TEENSY++") (pin "C1") (pinfunction "11_C1") (pintype "bidirectional"))
      (node (ref "X_MUX") (pin "10") (pinfunction "S0_10") (pintype "input"))
    )
    (net (code "105") (name "X_S1") (class "Default")
      (node (ref "TEENSY++") (pin "C0") (pinfunction "10_C0") (pintype "bidirectional"))
      (node (ref "X_MUX") (pin "11") (pinfunction "S1_11") (pintype "input"))
    )
    (net (code "106") (name "X_S2") (class "Default")
      (node (ref "TEENSY++") (pin "E1") (pinfunction "9_E1") (pintype "bidirectional"))
      (node (ref "X_MUX") (pin "14") (pinfunction "S2_14") (pintype "input"))
    )
    (net (code "107") (name "X_S3") (class "Default")
      (node (ref "TEENSY++") (pin "E0") (pinfunction "8_E0") (pintype "bidirectional"))
      (node (ref "X_MUX") (pin "13") (pinfunction "S3_13") (pintype "input"))
    )
    (net (code "108") (name "X_SIG") (class "Default")
      (node (ref "X_MUX") (pin "1") (pinfunction "COM_1") (pintype "bidirectional"))
    )
    (net (code "109") (name "Y_C0") (class "Default")
      (node (ref "Y_1") (pin "1") (pinfunction "1_1") (pintype "passive"))
      (node (ref "Y_MUX") (pin "9") (pinfunction "CHAN0_9") (pintype "bidirectional"))
    )
    (net (code "110") (name "Y_C1") (class "Default")
      (node (ref "Y_1") (pin "2") (pinfunction "2_2") (pintype "passive"))
      (node (ref "Y_MUX") (pin "8") (pinfunction "CHAN1_8") (pintype "bidirectional"))
    )
    (net (code "111") (name "Y_C2") (class "Default")
      (node (ref "Y_1") (pin "3") (pinfunction "3_3") (pintype "passive"))
      (node (ref "Y_MUX") (pin "7") (pinfunction "CHAN2_7") (pintype "bidirectional"))
    )
    (net (code "112") (name "Y_C3") (class "Default")
      (node (ref "Y_1") (pin "4") (pinfunction "4_4") (pintype "passive"))
      (node (ref "Y_MUX") (pin "6") (pinfunction "CHAN3_6") (pintype "bidirectional"))
    )
    (net (code "113") (name "Y_C4") (class "Default")
      (node (ref "Y_2") (pin "1") (pinfunction "1_1") (pintype "passive"))
      (node (ref "Y_MUX") (pin "5") (pinfunction "CHAN4_5") (pintype "bidirectional"))
    )
    (net (code "114") (name "Y_C5") (class "Default")
      (node (ref "Y_2") (pin "2") (pinfunction "2_2") (pintype "passive"))
      (node (ref "Y_MUX") (pin "4") (pinfunction "CHAN5_4") (pintype "bidirectional"))
    )
    (net (code "115") (name "Y_C6") (class "Default")
      (node (ref "Y_2") (pin "3") (pinfunction "3_3") (pintype "passive"))
      (node (ref "Y_MUX") (pin "3") (pinfunction "CHAN6_3") (pintype "bidirectional"))
    )
    (net (code "116") (name "Y_C7") (class "Default")
      (node (ref "Y_2") (pin "4") (pinfunction "4_4") (pintype "passive"))
      (node (ref "Y_MUX") (pin "2") (pinfunction "CHAN7_2") (pintype "bidirectional"))
    )
    (net (code "117") (name "Y_C8") (class "Default")
      (node (ref "Y_3") (pin "1") (pinfunction "1_1") (pintype "passive"))
      (node (ref "Y_MUX") (pin "23") (pinfunction "CHAN8_23") (pintype "bidirectional"))
    )
    (net (code "118") (name "Y_C9") (class "Default")
      (node (ref "Y_3") (pin "2") (pinfunction "2_2") (pintype "passive"))
      (node (ref "Y_MUX") (pin "22") (pinfunction "CHAN9_22") (pintype "bidirectional"))
    )
    (net (code "119") (name "Y_C10") (class "Default")
      (node (ref "Y_3") (pin "3") (pinfunction "3_3") (pintype "passive"))
      (node (ref "Y_MUX") (pin "21") (pinfunction "CHAN10_21") (pintype "bidirectional"))
    )
    (net (code "120") (name "Y_C11") (class "Default")
      (node (ref "Y_3") (pin "4") (pinfunction "4_4") (pintype "passive"))
      (node (ref "Y_MUX") (pin "20") (pinfunction "CHAN11_20") (pintype "bidirectional"))
    )
    (net (code "121") (name "Y_C12") (class "Default")
      (node (ref "Y_4") (pin "1") (pinfunction "1_1") (pintype "passive"))
      (node (ref "Y_MUX") (pin "19") (pinfunction "CHAN12_19") (pintype "bidirectional"))
    )
    (net (code "122") (name "Y_C13") (class "Default")
      (node (ref "Y_4") (pin "2") (pinfunction "2_2") (pintype "passive"))
      (node (ref "Y_MUX") (pin "18") (pinfunction "CHAN13_18") (pintype "bidirectional"))
    )
    (net (code "123") (name "Y_C14") (class "Default")
      (node (ref "Y_4") (pin "3") (pinfunction "3_3") (pintype "passive"))
      (node (ref "Y_MUX") (pin "17") (pinfunction "CHAN14_17") (pintype "bidirectional"))
    )
    (net (code "124") (name "Y_C15") (class "Default")
      (node (ref "Y_4") (pin "4") (pinfunction "4_4") (pintype "passive"))
      (node (ref "Y_MUX") (pin "16") (pinfunction "CHAN15_16") (pintype "bidirectional"))
    )
    (net (code "125") (name "Y_S0") (class "Default")
      (node (ref "TEENSY++") (pin "C5") (pinfunction "15,PWM_C5") (pintype "bidirectional"))
      (node (ref "Y_MUX") (pin "10") (pinfunction "S0_10") (pintype "input"))
    )
    (net (code "126") (name "Y_S1") (class "Default")
      (node (ref "TEENSY++") (pin "C4") (pinfunction "14,PWM_C4") (pintype "bidirectional"))
      (node (ref "Y_MUX") (pin "11") (pinfunction "S1_11") (pintype "input"))
    )
    (net (code "127") (name "Y_S2") (class "Default")
      (node (ref "TEENSY++") (pin "C3") (pinfunction "13_C3") (pintype "bidirectional"))
      (node (ref "Y_MUX") (pin "14") (pinfunction "S2_14") (pintype "input"))
    )
    (net (code "128") (name "Y_S3") (class "Default")
      (node (ref "TEENSY++") (pin "C2") (pinfunction "12_C2") (pintype "bidirectional"))
      (node (ref "Y_MUX") (pin "13") (pinfunction "S3_13") (pintype "input"))
    )
    (net (code "129") (name "Y_SIG") (class "Default")
      (node (ref "TEENSY++") (pin "F3") (pinfunction "41,A3_F3") (pintype "bidirectional"))
      (node (ref "Y_MUX") (pin "1") (pinfunction "COM_1") (pintype "bidirectional"))
    )
    (net (code "130") (name "unconnected-(TEENSY++-0,PWM,INT0-PadD0)") (class "Default")
      (node (ref "TEENSY++") (pin "D0") (pinfunction "0,PWM,INT0_D0") (pintype "bidirectional"))
    )
    (net (code "131") (name "unconnected-(TEENSY++-1,PWM,INT1-PadD1)") (class "Default")
      (node (ref "TEENSY++") (pin "D1") (pinfunction "1,PWM,INT1_D1") (pintype "bidirectional"))
    )
    (net (code "132") (name "unconnected-(TEENSY++-2,RX,INT2-PadD2)") (class "Default")
      (node (ref "TEENSY++") (pin "D2") (pinfunction "2,RX,INT2_D2") (pintype "bidirectional"))
    )
    (net (code "133") (name "unconnected-(TEENSY++-3,TX,INT3-PadD3)") (class "Default")
      (node (ref "TEENSY++") (pin "D3") (pinfunction "3,TX,INT3_D3") (pintype "bidirectional"))
    )
    (net (code "134") (name "unconnected-(TEENSY++-16,PWM-PadC6)") (class "Default")
      (node (ref "TEENSY++") (pin "C6") (pinfunction "16,PWM_C6") (pintype "bidirectional"))
    )
    (net (code "135") (name "unconnected-(TEENSY++-17-PadC7)") (class "Default")
      (node (ref "TEENSY++") (pin "C7") (pinfunction "17_C7") (pintype "bidirectional"))
    )
    (net (code "136") (name "unconnected-(TEENSY++-18,INT6-PadE6)") (class "Default")
      (node (ref "TEENSY++") (pin "E6") (pinfunction "18,INT6_E6") (pintype "bidirectional"))
    )
    (net (code "137") (name "unconnected-(TEENSY++-19-PadE7)") (class "Default")
      (node (ref "TEENSY++") (pin "E7") (pinfunction "19_E7") (pintype "bidirectional"))
    )
    (net (code "138") (name "unconnected-(TEENSY++-24,PWM-PadB4)") (class "Default")
      (node (ref "TEENSY++") (pin "B4") (pinfunction "24,PWM_B4") (pintype "bidirectional"))
    )
    (net (code "139") (name "unconnected-(TEENSY++-25,PWM-PadB5)") (class "Default")
      (node (ref "TEENSY++") (pin "B5") (pinfunction "25,PWM_B5") (pintype "bidirectional"))
    )
    (net (code "140") (name "unconnected-(TEENSY++-26,PWM-PadB6)") (class "Default")
      (node (ref "TEENSY++") (pin "B6") (pinfunction "26,PWM_B6") (pintype "bidirectional"))
    )
    (net (code "141") (name "unconnected-(TEENSY++-27,PWM-PadB7)") (class "Default")
      (node (ref "TEENSY++") (pin "B7") (pinfunction "27,PWM_B7") (pintype "bidirectional"))
    )
    (net (code "142") (name "unconnected-(TEENSY++-36,INT4-PadE4)") (class "Default")
      (node (ref "TEENSY++") (pin "E4") (pinfunction "36,INT4_E4") (pintype "bidirectional"))
    )
    (net (code "143") (name "unconnected-(TEENSY++-37,INT5-PadE5)") (class "Default")
      (node (ref "TEENSY++") (pin "E5") (pinfunction "37,INT5_E5") (pintype "bidirectional"))
    )
    (net (code "144") (name "unconnected-(TEENSY++-38,A0-PadF0)") (class "Default")
      (node (ref "TEENSY++") (pin "F0") (pinfunction "38,A0_F0") (pintype "bidirectional"))
    )
    (net (code "145") (name "unconnected-(TEENSY++-39,A1-PadF1)") (class "Default")
      (node (ref "TEENSY++") (pin "F1") (pinfunction "39,A1_F1") (pintype "bidirectional"))
    )
    (net (code "146") (name "unconnected-(TEENSY++-40,A2-PadF2)") (class "Default")
      (node (ref "TEENSY++") (pin "F2") (pinfunction "40,A2_F2") (pintype "bidirectional"))
    )
    (net (code "147") (name "unconnected-(TEENSY++-43,A5-PadF5)") (class "Default")
      (node (ref "TEENSY++") (pin "F5") (pinfunction "43,A5_F5") (pintype "bidirectional"))
    )
    (net (code "148") (name "unconnected-(TEENSY++-44,A6-PadF6)") (class "Default")
      (node (ref "TEENSY++") (pin "F6") (pinfunction "44,A6_F6") (pintype "bidirectional"))
    )
    (net (code "149") (name "unconnected-(TEENSY++-45,A7-PadF7)") (class "Default")
      (node (ref "TEENSY++") (pin "F7") (pinfunction "45,A7_F7") (pintype "bidirectional"))
    )
    (net (code "150") (name "unconnected-(TEENSY++-AREF-PadREF)") (class "Default")
      (node (ref "TEENSY++") (pin "REF") (pinfunction "AREF_REF") (pintype "input"))
    )
    (net (code "151") (name "unconnected-(TEENSY++-Pad+5V)") (class "Default")
      (node (ref "TEENSY++") (pin "+5V") (pinfunction "+5V_+5V") (pintype "power_in"))
    )
    (net (code "152") (name "unconnected-(TEENSY++-_RST-PadRST)") (class "Default")
      (node (ref "TEENSY++") (pin "RST") (pinfunction "_RST_RST") (pintype "input"))
    )
  )
)
